# U96-SVM.net
KiCad netlist of a schematic drawn in EAGLE
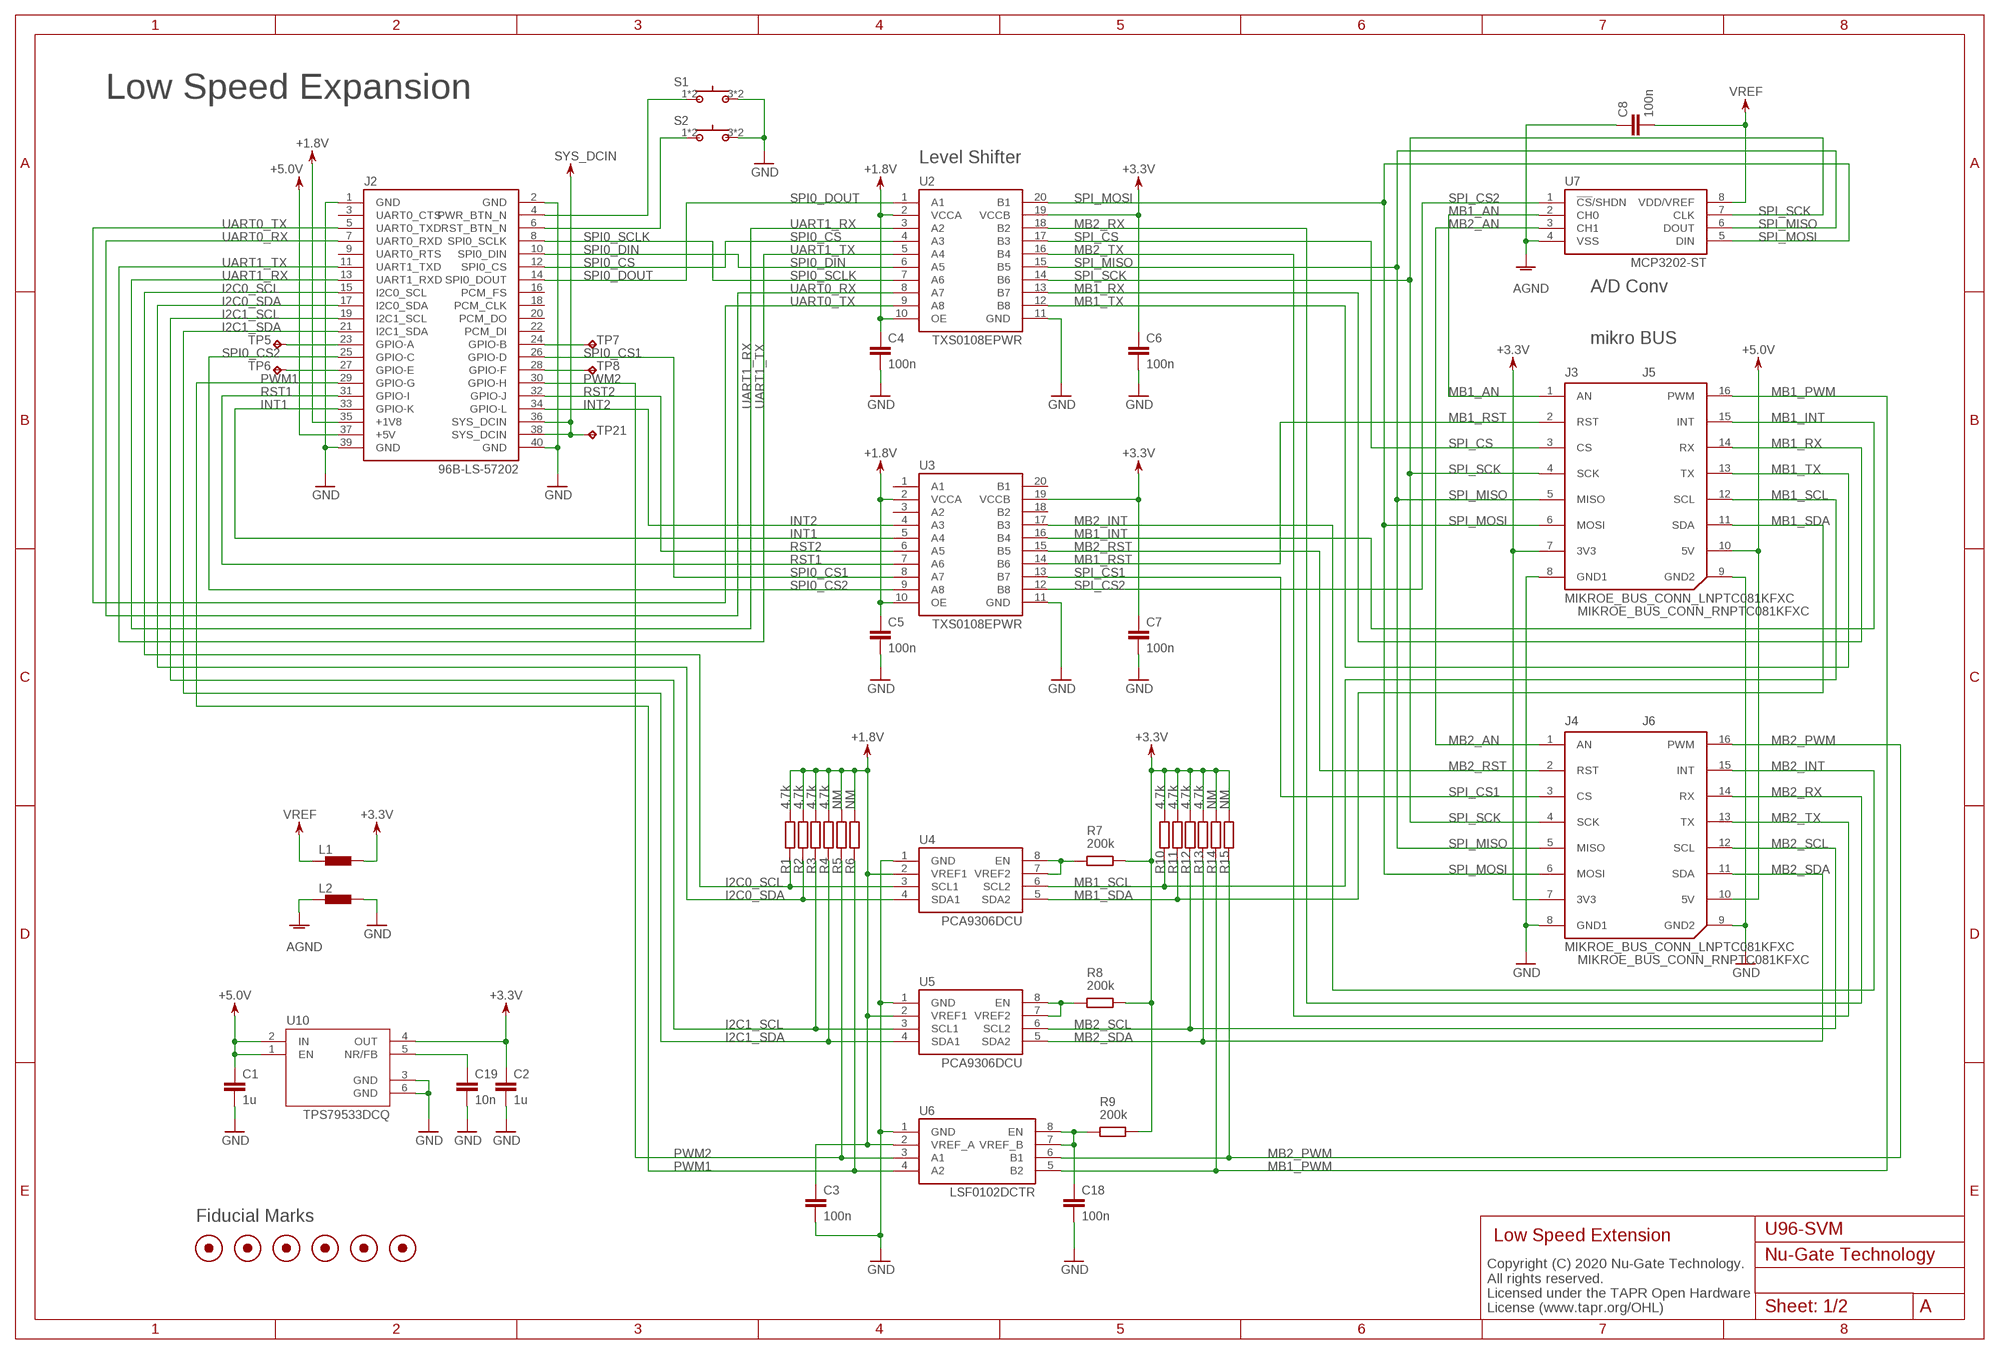
[diagram p0: schematic, sheet 1]
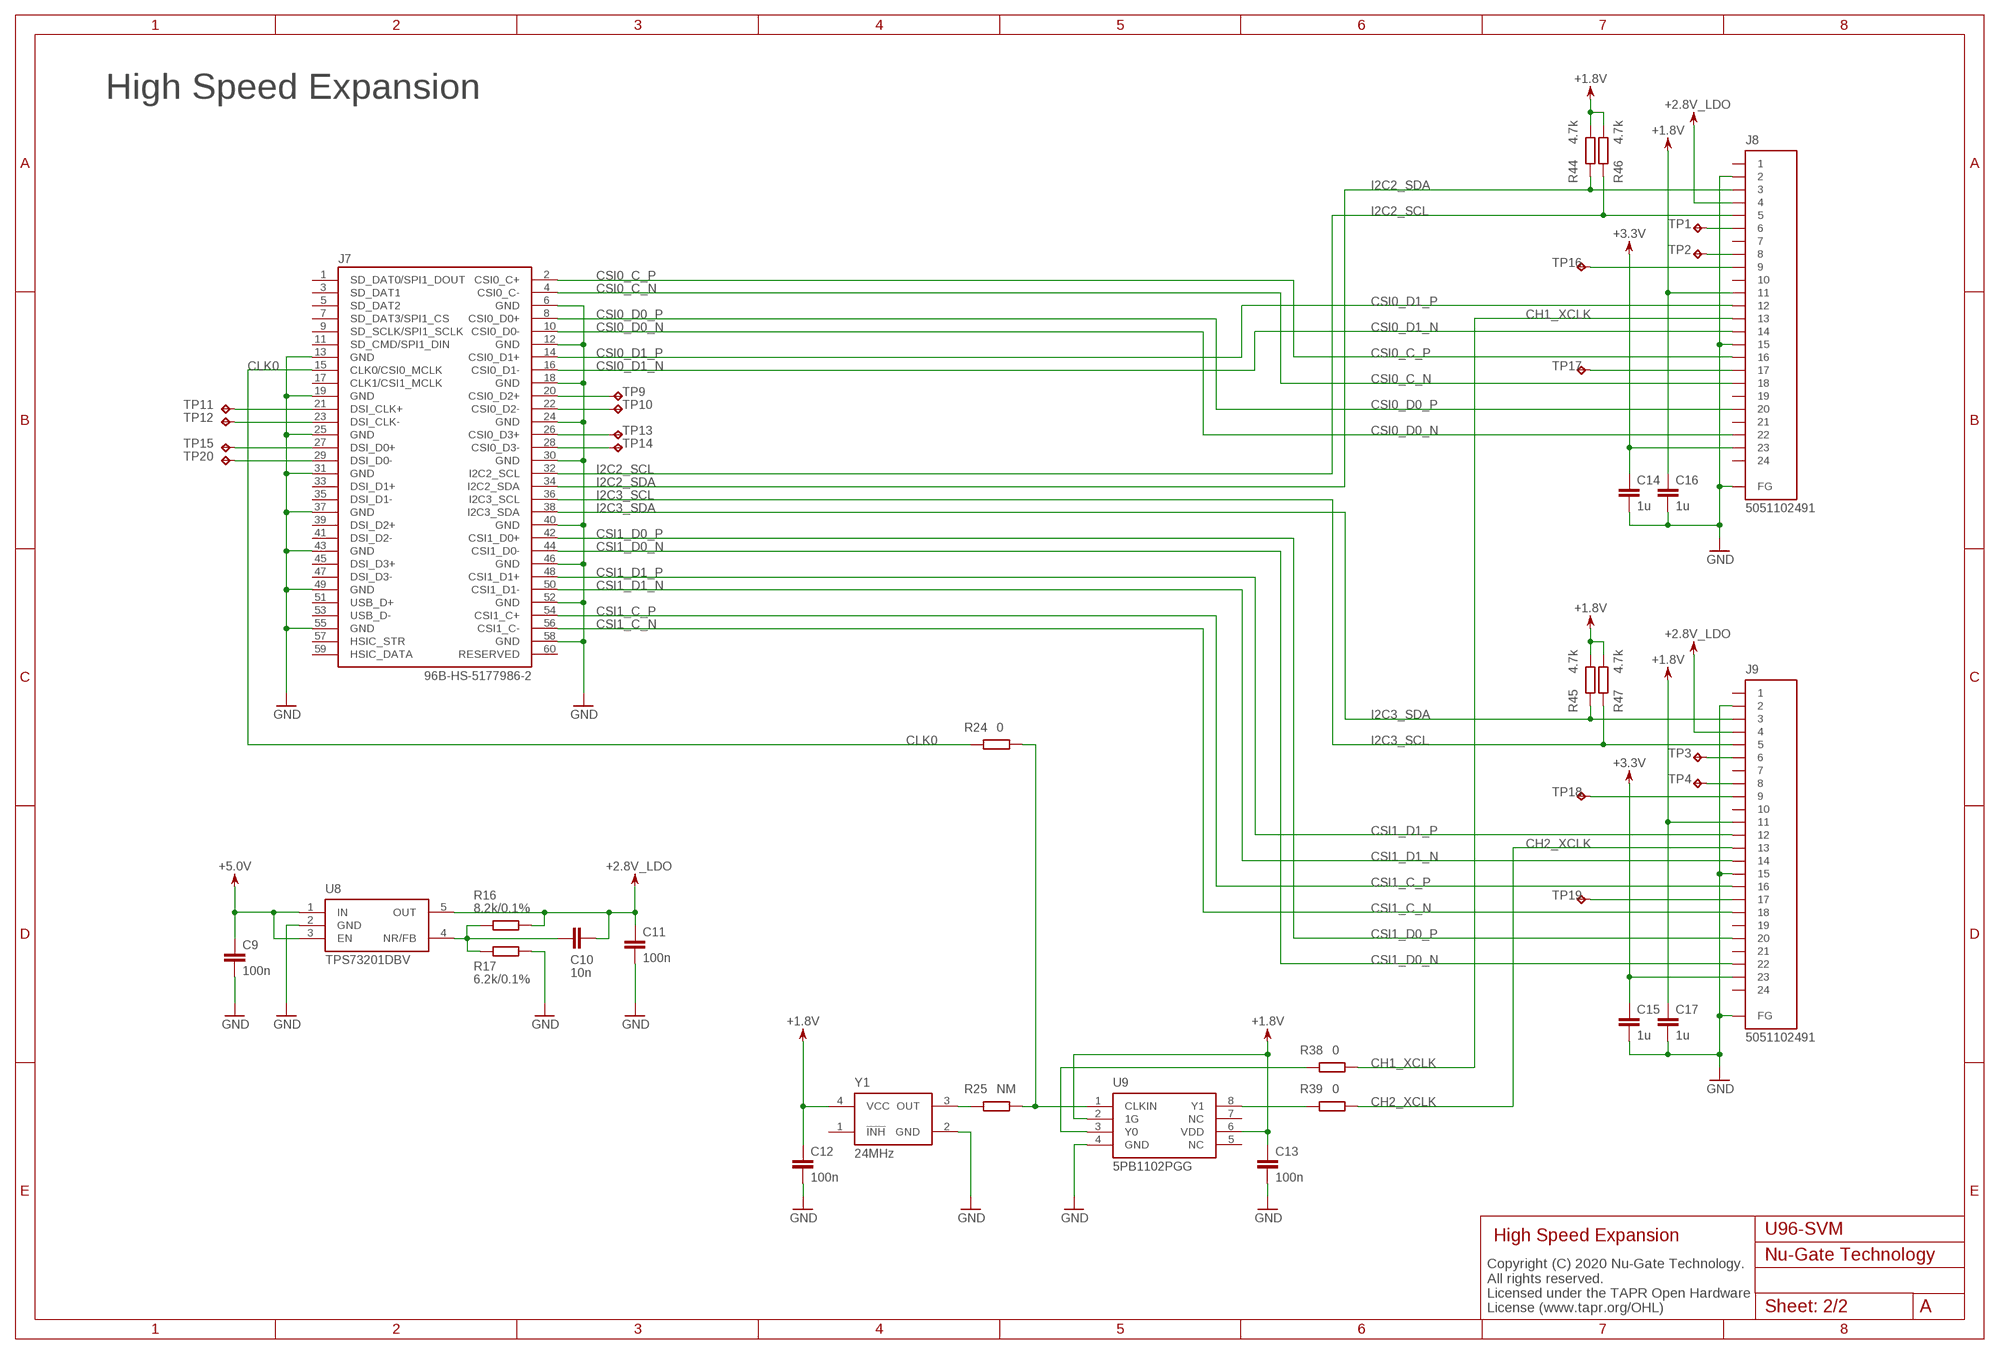
[diagram p1: schematic, sheet 2]

(export (version "E")
  (design (tool "Eeschema 10.0.6"))
  (components
    (comp (ref "C9")
      (value "100n")
      (footprint "eagle-import:C0402")
      (libsource (lib "eagle-import") (part "C-EUC0402"))
    )
    (comp (ref "C10")
      (value "10n")
      (footprint "eagle-import:C0402")
      (libsource (lib "eagle-import") (part "C-EUC0402"))
    )
    (comp (ref "C11")
      (value "100n")
      (footprint "eagle-import:C0402")
      (libsource (lib "eagle-import") (part "C-EUC0402"))
    )
    (comp (ref "C12")
      (value "100n")
      (footprint "eagle-import:C0402")
      (libsource (lib "eagle-import") (part "C-EUC0402"))
    )
    (comp (ref "C13")
      (value "100n")
      (footprint "eagle-import:C0402")
      (libsource (lib "eagle-import") (part "C-EUC0402"))
    )
    (comp (ref "C14")
      (value "1u")
      (footprint "eagle-import:C0402")
      (libsource (lib "eagle-import") (part "C-EUC0402"))
    )
    (comp (ref "C15")
      (value "1u")
      (footprint "eagle-import:C0402")
      (libsource (lib "eagle-import") (part "C-EUC0402"))
    )
    (comp (ref "C16")
      (value "1u")
      (footprint "eagle-import:C0402")
      (libsource (lib "eagle-import") (part "C-EUC0402"))
    )
    (comp (ref "C17")
      (value "1u")
      (footprint "eagle-import:C0402")
      (libsource (lib "eagle-import") (part "C-EUC0402"))
    )
    (comp (ref "J7")
      (value "96B-HS-5177986-2")
      (footprint "eagle-import:5177986-2")
      (libsource (lib "eagle-import") (part "96B-HS-5177986-2"))
    )
    (comp (ref "J8")
      (value "5051102491")
      (footprint "eagle-import:MO-5051102491")
      (libsource (lib "eagle-import") (part "5051102491"))
    )
    (comp (ref "J9")
      (value "5051102491")
      (footprint "eagle-import:MO-5051102491")
      (libsource (lib "eagle-import") (part "5051102491"))
    )
    (comp (ref "R16")
      (value "8.2k/0.1%")
      (footprint "eagle-import:R0402")
      (libsource (lib "eagle-import") (part "R-EU_R0402"))
    )
    (comp (ref "R17")
      (value "6.2k/0.1%")
      (footprint "eagle-import:R0402")
      (libsource (lib "eagle-import") (part "R-EU_R0402"))
    )
    (comp (ref "R24")
      (value "0")
      (footprint "eagle-import:R0402")
      (libsource (lib "eagle-import") (part "R-EU_R0402"))
    )
    (comp (ref "R25")
      (value "NM")
      (footprint "eagle-import:R0402")
      (libsource (lib "eagle-import") (part "R-EU_R0402"))
    )
    (comp (ref "R38")
      (value "0")
      (footprint "eagle-import:R0402")
      (libsource (lib "eagle-import") (part "R-EU_R0402"))
    )
    (comp (ref "R39")
      (value "0")
      (footprint "eagle-import:R0402")
      (libsource (lib "eagle-import") (part "R-EU_R0402"))
    )
    (comp (ref "R44")
      (value "4.7k")
      (footprint "eagle-import:R0402")
      (libsource (lib "eagle-import") (part "R-EU_R0402"))
    )
    (comp (ref "R45")
      (value "4.7k")
      (footprint "eagle-import:R0402")
      (libsource (lib "eagle-import") (part "R-EU_R0402"))
    )
    (comp (ref "R46")
      (value "4.7k")
      (footprint "eagle-import:R0402")
      (libsource (lib "eagle-import") (part "R-EU_R0402"))
    )
    (comp (ref "R47")
      (value "4.7k")
      (footprint "eagle-import:R0402")
      (libsource (lib "eagle-import") (part "R-EU_R0402"))
    )
    (comp (ref "TP1")
      (value "TPB1,27")
      (footprint "eagle-import:B1,27")
      (libsource (lib "eagle-import") (part "TPB1,27"))
    )
    (comp (ref "TP2")
      (value "TPB1,27")
      (footprint "eagle-import:B1,27")
      (libsource (lib "eagle-import") (part "TPB1,27"))
    )
    (comp (ref "TP3")
      (value "TPB1,27")
      (footprint "eagle-import:B1,27")
      (libsource (lib "eagle-import") (part "TPB1,27"))
    )
    (comp (ref "TP4")
      (value "TPB1,27")
      (footprint "eagle-import:B1,27")
      (libsource (lib "eagle-import") (part "TPB1,27"))
    )
    (comp (ref "TP9")
      (value "TPB1,27")
      (footprint "eagle-import:B1,27")
      (libsource (lib "eagle-import") (part "TPB1,27"))
    )
    (comp (ref "TP10")
      (value "TPB1,27")
      (footprint "eagle-import:B1,27")
      (libsource (lib "eagle-import") (part "TPB1,27"))
    )
    (comp (ref "TP11")
      (value "TPB1,27")
      (footprint "eagle-import:B1,27")
      (libsource (lib "eagle-import") (part "TPB1,27"))
    )
    (comp (ref "TP12")
      (value "TPB1,27")
      (footprint "eagle-import:B1,27")
      (libsource (lib "eagle-import") (part "TPB1,27"))
    )
    (comp (ref "TP13")
      (value "TPB1,27")
      (footprint "eagle-import:B1,27")
      (libsource (lib "eagle-import") (part "TPB1,27"))
    )
    (comp (ref "TP14")
      (value "TPB1,27")
      (footprint "eagle-import:B1,27")
      (libsource (lib "eagle-import") (part "TPB1,27"))
    )
    (comp (ref "TP15")
      (value "TPB1,27")
      (footprint "eagle-import:B1,27")
      (libsource (lib "eagle-import") (part "TPB1,27"))
    )
    (comp (ref "TP16")
      (value "TPB1,27")
      (footprint "eagle-import:B1,27")
      (libsource (lib "eagle-import") (part "TPB1,27"))
    )
    (comp (ref "TP17")
      (value "TPB1,27")
      (footprint "eagle-import:B1,27")
      (libsource (lib "eagle-import") (part "TPB1,27"))
    )
    (comp (ref "TP18")
      (value "TPB1,27")
      (footprint "eagle-import:B1,27")
      (libsource (lib "eagle-import") (part "TPB1,27"))
    )
    (comp (ref "TP19")
      (value "TPB1,27")
      (footprint "eagle-import:B1,27")
      (libsource (lib "eagle-import") (part "TPB1,27"))
    )
    (comp (ref "TP20")
      (value "TPB1,27")
      (footprint "eagle-import:B1,27")
      (libsource (lib "eagle-import") (part "TPB1,27"))
    )
    (comp (ref "U8")
      (value "TPS73201DBV")
      (footprint "eagle-import:TI-SOT23")
      (libsource (lib "eagle-import") (part "TPS732DBV01"))
    )
    (comp (ref "U9")
      (value "5PB1102PGG")
      (footprint "eagle-import:ID-TSSOP8")
      (libsource (lib "eagle-import") (part "5PB1102PGG"))
    )
    (comp (ref "Y1")
      (value "24MHz")
      (footprint "eagle-import:KC2520Z")
      (libsource (lib "eagle-import") (part "KC2520Z"))
    )
    (comp (ref "C1")
      (value "1u")
      (footprint "eagle-import:C0402")
      (libsource (lib "eagle-import") (part "C-EUC0402"))
    )
    (comp (ref "C2")
      (value "1u")
      (footprint "eagle-import:C0402")
      (libsource (lib "eagle-import") (part "C-EUC0402"))
    )
    (comp (ref "C3")
      (value "100n")
      (footprint "eagle-import:C0402")
      (libsource (lib "eagle-import") (part "C-EUC0402"))
    )
    (comp (ref "C4")
      (value "100n")
      (footprint "eagle-import:C0402")
      (libsource (lib "eagle-import") (part "C-EUC0402"))
    )
    (comp (ref "C5")
      (value "100n")
      (footprint "eagle-import:C0402")
      (libsource (lib "eagle-import") (part "C-EUC0402"))
    )
    (comp (ref "C6")
      (value "100n")
      (footprint "eagle-import:C0402")
      (libsource (lib "eagle-import") (part "C-EUC0402"))
    )
    (comp (ref "C7")
      (value "100n")
      (footprint "eagle-import:C0402")
      (libsource (lib "eagle-import") (part "C-EUC0402"))
    )
    (comp (ref "C8")
      (value "100n")
      (footprint "eagle-import:C0402")
      (libsource (lib "eagle-import") (part "C-EUC0402"))
    )
    (comp (ref "C18")
      (value "100n")
      (footprint "eagle-import:C0402")
      (libsource (lib "eagle-import") (part "C-EUC0402"))
    )
    (comp (ref "C19")
      (value "10n")
      (footprint "eagle-import:C0402")
      (libsource (lib "eagle-import") (part "C-EUC0402"))
    )
    (comp (ref "FID1")
      (value "FIDUCIAL")
      (footprint "eagle-import:FIDUCIAL_1MM")
      (libsource (lib "eagle-import") (part "FIDUCIAL"))
    )
    (comp (ref "FID2")
      (value "FIDUCIAL")
      (footprint "eagle-import:FIDUCIAL_1MM")
      (libsource (lib "eagle-import") (part "FIDUCIAL"))
    )
    (comp (ref "FID3")
      (value "FIDUCIAL")
      (footprint "eagle-import:FIDUCIAL_1MM")
      (libsource (lib "eagle-import") (part "FIDUCIAL"))
    )
    (comp (ref "FID4")
      (value "FIDUCIAL")
      (footprint "eagle-import:FIDUCIAL_1MM")
      (libsource (lib "eagle-import") (part "FIDUCIAL"))
    )
    (comp (ref "FID5")
      (value "FIDUCIAL")
      (footprint "eagle-import:FIDUCIAL_1MM")
      (libsource (lib "eagle-import") (part "FIDUCIAL"))
    )
    (comp (ref "FID6")
      (value "FIDUCIAL")
      (footprint "eagle-import:FIDUCIAL_1MM")
      (libsource (lib "eagle-import") (part "FIDUCIAL"))
    )
    (comp (ref "J2")
      (value "96B-LS-57202")
      (footprint "eagle-import:57202-G52-20LF")
      (libsource (lib "eagle-import") (part "96B-LS-57202"))
    )
    (comp (ref "J3")
      (value "MIKROE_BUS_CONN_LNPTC081KFXC")
      (footprint "eagle-import:MIKROBUS_HOST_CONN_L2")
      (libsource (lib "eagle-import") (part "MIKROE_BUS_CONN_LNPTC081KFXC"))
    )
    (comp (ref "J4")
      (value "MIKROE_BUS_CONN_LNPTC081KFXC")
      (footprint "eagle-import:MIKROBUS_HOST_CONN_L2")
      (libsource (lib "eagle-import") (part "MIKROE_BUS_CONN_LNPTC081KFXC"))
    )
    (comp (ref "J5")
      (value "MIKROE_BUS_CONN_RNPTC081KFXC")
      (footprint "eagle-import:MIKROBUS_HOST_CONN_R2")
      (libsource (lib "eagle-import") (part "MIKROE_BUS_CONN_RNPTC081KFXC"))
    )
    (comp (ref "J6")
      (value "MIKROE_BUS_CONN_RNPTC081KFXC")
      (footprint "eagle-import:MIKROBUS_HOST_CONN_R2")
      (libsource (lib "eagle-import") (part "MIKROE_BUS_CONN_RNPTC081KFXC"))
    )
    (comp (ref "L1")
      (value "BLM15AX")
      (footprint "eagle-import:0402")
      (libsource (lib "eagle-import") (part "BLM15AX"))
    )
    (comp (ref "L2")
      (value "BLM15AX")
      (footprint "eagle-import:0402")
      (libsource (lib "eagle-import") (part "BLM15AX"))
    )
    (comp (ref "R1")
      (value "4.7k")
      (footprint "eagle-import:R0402")
      (libsource (lib "eagle-import") (part "R-EU_R0402"))
    )
    (comp (ref "R2")
      (value "4.7k")
      (footprint "eagle-import:R0402")
      (libsource (lib "eagle-import") (part "R-EU_R0402"))
    )
    (comp (ref "R3")
      (value "4.7k")
      (footprint "eagle-import:R0402")
      (libsource (lib "eagle-import") (part "R-EU_R0402"))
    )
    (comp (ref "R4")
      (value "4.7k")
      (footprint "eagle-import:R0402")
      (libsource (lib "eagle-import") (part "R-EU_R0402"))
    )
    (comp (ref "R5")
      (value "NM")
      (footprint "eagle-import:R0402")
      (libsource (lib "eagle-import") (part "R-EU_R0402"))
    )
    (comp (ref "R6")
      (value "NM")
      (footprint "eagle-import:R0402")
      (libsource (lib "eagle-import") (part "R-EU_R0402"))
    )
    (comp (ref "R7")
      (value "200k")
      (footprint "eagle-import:R0402")
      (libsource (lib "eagle-import") (part "R-EU_R0402"))
    )
    (comp (ref "R8")
      (value "200k")
      (footprint "eagle-import:R0402")
      (libsource (lib "eagle-import") (part "R-EU_R0402"))
    )
    (comp (ref "R9")
      (value "200k")
      (footprint "eagle-import:R0402")
      (libsource (lib "eagle-import") (part "R-EU_R0402"))
    )
    (comp (ref "R10")
      (value "4.7k")
      (footprint "eagle-import:R0402")
      (libsource (lib "eagle-import") (part "R-EU_R0402"))
    )
    (comp (ref "R11")
      (value "4.7k")
      (footprint "eagle-import:R0402")
      (libsource (lib "eagle-import") (part "R-EU_R0402"))
    )
    (comp (ref "R12")
      (value "4.7k")
      (footprint "eagle-import:R0402")
      (libsource (lib "eagle-import") (part "R-EU_R0402"))
    )
    (comp (ref "R13")
      (value "4.7k")
      (footprint "eagle-import:R0402")
      (libsource (lib "eagle-import") (part "R-EU_R0402"))
    )
    (comp (ref "R14")
      (value "NM")
      (footprint "eagle-import:R0402")
      (libsource (lib "eagle-import") (part "R-EU_R0402"))
    )
    (comp (ref "R15")
      (value "NM")
      (footprint "eagle-import:R0402")
      (libsource (lib "eagle-import") (part "R-EU_R0402"))
    )
    (comp (ref "S1")
      (value "430181038816")
      (footprint "eagle-import:430181038816")
      (libsource (lib "eagle-import") (part "430181038816"))
    )
    (comp (ref "S2")
      (value "430181038816")
      (footprint "eagle-import:430181038816")
      (libsource (lib "eagle-import") (part "430181038816"))
    )
    (comp (ref "TP5")
      (value "TPB1,27")
      (footprint "eagle-import:B1,27")
      (libsource (lib "eagle-import") (part "TPB1,27"))
    )
    (comp (ref "TP6")
      (value "TPB1,27")
      (footprint "eagle-import:B1,27")
      (libsource (lib "eagle-import") (part "TPB1,27"))
    )
    (comp (ref "TP7")
      (value "TPB1,27")
      (footprint "eagle-import:B1,27")
      (libsource (lib "eagle-import") (part "TPB1,27"))
    )
    (comp (ref "TP8")
      (value "TPB1,27")
      (footprint "eagle-import:B1,27")
      (libsource (lib "eagle-import") (part "TPB1,27"))
    )
    (comp (ref "TP21")
      (value "TPB1,27")
      (footprint "eagle-import:B1,27")
      (libsource (lib "eagle-import") (part "TPB1,27"))
    )
    (comp (ref "U2")
      (value "TXS0108EPWR")
      (footprint "eagle-import:TI-PW20")
      (libsource (lib "eagle-import") (part "TXS0108EPWR"))
    )
    (comp (ref "U3")
      (value "TXS0108EPWR")
      (footprint "eagle-import:TI-PW20")
      (libsource (lib "eagle-import") (part "TXS0108EPWR"))
    )
    (comp (ref "U4")
      (value "PCA9306DCU")
      (footprint "eagle-import:TI-DCU8")
      (libsource (lib "eagle-import") (part "PCA9306DCU"))
    )
    (comp (ref "U5")
      (value "PCA9306DCU")
      (footprint "eagle-import:TI-DCU8")
      (libsource (lib "eagle-import") (part "PCA9306DCU"))
    )
    (comp (ref "U6")
      (value "LSF0102DCTR")
      (footprint "eagle-import:TI-DCT8")
      (libsource (lib "eagle-import") (part "LSF0102DCTR"))
    )
    (comp (ref "U7")
      (value "MCP3202-ST")
      (footprint "eagle-import:MC-ST8")
      (libsource (lib "eagle-import") (part "MCP3202-ST"))
    )
    (comp (ref "U10")
      (value "TPS79533DCQ")
      (footprint "eagle-import:TI-SOT223")
      (libsource (lib "eagle-import") (part "TPS79533DCQ"))
    )
  )
  (nets
    (net (code "1") (name "+1.8V") (class "Default")
      (node (ref "C12") (pin "1") (pinfunction "1_1") (pintype "passive"))
      (node (ref "C13") (pin "1") (pinfunction "1_1") (pintype "passive"))
      (node (ref "C16") (pin "1") (pinfunction "1_1") (pintype "passive"))
      (node (ref "C17") (pin "1") (pinfunction "1_1") (pintype "passive"))
      (node (ref "C3") (pin "1") (pinfunction "1_1") (pintype "passive"))
      (node (ref "C4") (pin "1") (pinfunction "1_1") (pintype "passive"))
      (node (ref "C5") (pin "1") (pinfunction "1_1") (pintype "passive"))
      (node (ref "J2") (pin "35") (pinfunction "+1V8_35") (pintype "bidirectional"))
      (node (ref "J8") (pin "11") (pinfunction "11_11") (pintype "bidirectional"))
      (node (ref "J9") (pin "11") (pinfunction "11_11") (pintype "bidirectional"))
      (node (ref "R1") (pin "2") (pinfunction "2_2") (pintype "passive"))
      (node (ref "R2") (pin "2") (pinfunction "2_2") (pintype "passive"))
      (node (ref "R3") (pin "2") (pinfunction "2_2") (pintype "passive"))
      (node (ref "R4") (pin "2") (pinfunction "2_2") (pintype "passive"))
      (node (ref "R44") (pin "2") (pinfunction "2_2") (pintype "passive"))
      (node (ref "R45") (pin "2") (pinfunction "2_2") (pintype "passive"))
      (node (ref "R46") (pin "2") (pinfunction "2_2") (pintype "passive"))
      (node (ref "R47") (pin "2") (pinfunction "2_2") (pintype "passive"))
      (node (ref "R5") (pin "2") (pinfunction "2_2") (pintype "passive"))
      (node (ref "R6") (pin "2") (pinfunction "2_2") (pintype "passive"))
      (node (ref "U2") (pin "10") (pinfunction "OE_10") (pintype "bidirectional"))
      (node (ref "U2") (pin "2") (pinfunction "VCCA_2") (pintype "bidirectional"))
      (node (ref "U3") (pin "10") (pinfunction "OE_10") (pintype "bidirectional"))
      (node (ref "U3") (pin "2") (pinfunction "VCCA_2") (pintype "bidirectional"))
      (node (ref "U4") (pin "2") (pinfunction "VREF1_2") (pintype "bidirectional"))
      (node (ref "U5") (pin "2") (pinfunction "VREF1_2") (pintype "bidirectional"))
      (node (ref "U6") (pin "2") (pinfunction "VREF_A_2") (pintype "bidirectional"))
      (node (ref "U9") (pin "2") (pinfunction "1G_2") (pintype "bidirectional"))
      (node (ref "U9") (pin "6") (pinfunction "VDD_6") (pintype "bidirectional"))
      (node (ref "Y1") (pin "4") (pinfunction "VCC_4") (pintype "power_in"))
    )
    (net (code "2") (name "+2.8V_LDO") (class "Default")
      (node (ref "C10") (pin "2") (pinfunction "2_2") (pintype "passive"))
      (node (ref "C11") (pin "1") (pinfunction "1_1") (pintype "passive"))
      (node (ref "J8") (pin "4") (pinfunction "4_4") (pintype "bidirectional"))
      (node (ref "J9") (pin "4") (pinfunction "4_4") (pintype "bidirectional"))
      (node (ref "R16") (pin "2") (pinfunction "2_2") (pintype "passive"))
      (node (ref "U8") (pin "5") (pinfunction "OUT_5") (pintype "power_in"))
    )
    (net (code "3") (name "+3.3V") (class "Default")
      (node (ref "C14") (pin "1") (pinfunction "1_1") (pintype "passive"))
      (node (ref "C15") (pin "1") (pinfunction "1_1") (pintype "passive"))
      (node (ref "C2") (pin "1") (pinfunction "1_1") (pintype "passive"))
      (node (ref "C6") (pin "1") (pinfunction "1_1") (pintype "passive"))
      (node (ref "C7") (pin "1") (pinfunction "1_1") (pintype "passive"))
      (node (ref "J3") (pin "7") (pinfunction "3V3_7") (pintype "bidirectional"))
      (node (ref "J4") (pin "7") (pinfunction "3V3_7") (pintype "bidirectional"))
      (node (ref "J8") (pin "23") (pinfunction "23_23") (pintype "bidirectional"))
      (node (ref "J9") (pin "23") (pinfunction "23_23") (pintype "bidirectional"))
      (node (ref "L1") (pin "2") (pinfunction "2_2") (pintype "passive"))
      (node (ref "R10") (pin "2") (pinfunction "2_2") (pintype "passive"))
      (node (ref "R11") (pin "2") (pinfunction "2_2") (pintype "passive"))
      (node (ref "R12") (pin "2") (pinfunction "2_2") (pintype "passive"))
      (node (ref "R13") (pin "2") (pinfunction "2_2") (pintype "passive"))
      (node (ref "R14") (pin "2") (pinfunction "2_2") (pintype "passive"))
      (node (ref "R15") (pin "2") (pinfunction "2_2") (pintype "passive"))
      (node (ref "R7") (pin "2") (pinfunction "2_2") (pintype "passive"))
      (node (ref "R8") (pin "2") (pinfunction "2_2") (pintype "passive"))
      (node (ref "R9") (pin "2") (pinfunction "2_2") (pintype "passive"))
      (node (ref "U10") (pin "4") (pinfunction "OUT_4") (pintype "bidirectional"))
      (node (ref "U2") (pin "19") (pinfunction "VCCB_19") (pintype "bidirectional"))
      (node (ref "U3") (pin "19") (pinfunction "VCCB_19") (pintype "bidirectional"))
    )
    (net (code "4") (name "+5.0V") (class "Default")
      (node (ref "C1") (pin "1") (pinfunction "1_1") (pintype "passive"))
      (node (ref "C9") (pin "1") (pinfunction "1_1") (pintype "passive"))
      (node (ref "J2") (pin "37") (pinfunction "+5V_37") (pintype "bidirectional"))
      (node (ref "J5") (pin "10") (pinfunction "5V_10") (pintype "bidirectional"))
      (node (ref "J6") (pin "10") (pinfunction "5V_10") (pintype "bidirectional"))
      (node (ref "U10") (pin "1") (pinfunction "EN_1") (pintype "bidirectional"))
      (node (ref "U10") (pin "2") (pinfunction "IN_2") (pintype "bidirectional"))
      (node (ref "U8") (pin "1") (pinfunction "IN_1") (pintype "power_in"))
      (node (ref "U8") (pin "3") (pinfunction "EN_3") (pintype "input"))
    )
    (net (code "5") (name "AGND") (class "Default")
      (node (ref "C8") (pin "1") (pinfunction "1_1") (pintype "passive"))
      (node (ref "L2") (pin "1") (pinfunction "1_1") (pintype "passive"))
      (node (ref "U7") (pin "4") (pinfunction "VSS_4") (pintype "bidirectional"))
    )
    (net (code "6") (name "CH1_XCLK") (class "Default")
      (node (ref "J8") (pin "13") (pinfunction "13_13") (pintype "bidirectional"))
      (node (ref "R38") (pin "2") (pinfunction "2_2") (pintype "passive"))
    )
    (net (code "7") (name "CH2_XCLK") (class "Default")
      (node (ref "J9") (pin "13") (pinfunction "13_13") (pintype "bidirectional"))
      (node (ref "R39") (pin "2") (pinfunction "2_2") (pintype "passive"))
    )
    (net (code "8") (name "CLK0") (class "Default")
      (node (ref "J7") (pin "15") (pinfunction "CLK0/CSI0_MCLK_15") (pintype "bidirectional"))
      (node (ref "R24") (pin "1") (pinfunction "1_1") (pintype "passive"))
    )
    (net (code "9") (name "CSI0_C_N") (class "Default")
      (node (ref "J7") (pin "4") (pinfunction "CSI0_C-_4") (pintype "bidirectional"))
      (node (ref "J8") (pin "18") (pinfunction "18_18") (pintype "bidirectional"))
    )
    (net (code "10") (name "CSI0_C_P") (class "Default")
      (node (ref "J7") (pin "2") (pinfunction "CSI0_C+_2") (pintype "bidirectional"))
      (node (ref "J8") (pin "16") (pinfunction "16_16") (pintype "bidirectional"))
    )
    (net (code "11") (name "CSI0_D0_N") (class "Default")
      (node (ref "J7") (pin "10") (pinfunction "CSI0_D0-_10") (pintype "bidirectional"))
      (node (ref "J8") (pin "22") (pinfunction "22_22") (pintype "bidirectional"))
    )
    (net (code "12") (name "CSI0_D0_P") (class "Default")
      (node (ref "J7") (pin "8") (pinfunction "CSI0_D0+_8") (pintype "bidirectional"))
      (node (ref "J8") (pin "20") (pinfunction "20_20") (pintype "bidirectional"))
    )
    (net (code "13") (name "CSI0_D1_N") (class "Default")
      (node (ref "J7") (pin "16") (pinfunction "CSI0_D1-_16") (pintype "bidirectional"))
      (node (ref "J8") (pin "14") (pinfunction "14_14") (pintype "bidirectional"))
    )
    (net (code "14") (name "CSI0_D1_P") (class "Default")
      (node (ref "J7") (pin "14") (pinfunction "CSI0_D1+_14") (pintype "bidirectional"))
      (node (ref "J8") (pin "12") (pinfunction "12_12") (pintype "bidirectional"))
    )
    (net (code "15") (name "CSI1_C_N") (class "Default")
      (node (ref "J7") (pin "56") (pinfunction "CSI1_C-_56") (pintype "bidirectional"))
      (node (ref "J9") (pin "18") (pinfunction "18_18") (pintype "bidirectional"))
    )
    (net (code "16") (name "CSI1_C_P") (class "Default")
      (node (ref "J7") (pin "54") (pinfunction "CSI1_C+_54") (pintype "bidirectional"))
      (node (ref "J9") (pin "16") (pinfunction "16_16") (pintype "bidirectional"))
    )
    (net (code "17") (name "CSI1_D0_N") (class "Default")
      (node (ref "J7") (pin "44") (pinfunction "CSI1_D0-_44") (pintype "bidirectional"))
      (node (ref "J9") (pin "22") (pinfunction "22_22") (pintype "bidirectional"))
    )
    (net (code "18") (name "CSI1_D0_P") (class "Default")
      (node (ref "J7") (pin "42") (pinfunction "CSI1_D0+_42") (pintype "bidirectional"))
      (node (ref "J9") (pin "20") (pinfunction "20_20") (pintype "bidirectional"))
    )
    (net (code "19") (name "CSI1_D1_N") (class "Default")
      (node (ref "J7") (pin "50") (pinfunction "CSI1_D1-_50") (pintype "bidirectional"))
      (node (ref "J9") (pin "14") (pinfunction "14_14") (pintype "bidirectional"))
    )
    (net (code "20") (name "CSI1_D1_P") (class "Default")
      (node (ref "J7") (pin "48") (pinfunction "CSI1_D1+_48") (pintype "bidirectional"))
      (node (ref "J9") (pin "12") (pinfunction "12_12") (pintype "bidirectional"))
    )
    (net (code "21") (name "GND") (class "Default")
      (node (ref "C1") (pin "2") (pinfunction "2_2") (pintype "passive"))
      (node (ref "C11") (pin "2") (pinfunction "2_2") (pintype "passive"))
      (node (ref "C12") (pin "2") (pinfunction "2_2") (pintype "passive"))
      (node (ref "C13") (pin "2") (pinfunction "2_2") (pintype "passive"))
      (node (ref "C14") (pin "2") (pinfunction "2_2") (pintype "passive"))
      (node (ref "C15") (pin "2") (pinfunction "2_2") (pintype "passive"))
      (node (ref "C16") (pin "2") (pinfunction "2_2") (pintype "passive"))
      (node (ref "C17") (pin "2") (pinfunction "2_2") (pintype "passive"))
      (node (ref "C18") (pin "2") (pinfunction "2_2") (pintype "passive"))
      (node (ref "C19") (pin "2") (pinfunction "2_2") (pintype "passive"))
      (node (ref "C2") (pin "2") (pinfunction "2_2") (pintype "passive"))
      (node (ref "C3") (pin "2") (pinfunction "2_2") (pintype "passive"))
      (node (ref "C4") (pin "2") (pinfunction "2_2") (pintype "passive"))
      (node (ref "C5") (pin "2") (pinfunction "2_2") (pintype "passive"))
      (node (ref "C6") (pin "2") (pinfunction "2_2") (pintype "passive"))
      (node (ref "C7") (pin "2") (pinfunction "2_2") (pintype "passive"))
      (node (ref "C9") (pin "2") (pinfunction "2_2") (pintype "passive"))
      (node (ref "J2") (pin "1") (pinfunction "GND_1") (pintype "bidirectional"))
      (node (ref "J2") (pin "2") (pinfunction "GND_2") (pintype "bidirectional"))
      (node (ref "J2") (pin "39") (pinfunction "GND_39") (pintype "bidirectional"))
      (node (ref "J2") (pin "40") (pinfunction "GND_40") (pintype "bidirectional"))
      (node (ref "J3") (pin "8") (pinfunction "GND1_8") (pintype "bidirectional"))
      (node (ref "J4") (pin "8") (pinfunction "GND1_8") (pintype "bidirectional"))
      (node (ref "J5") (pin "9") (pinfunction "GND2_9") (pintype "bidirectional"))
      (node (ref "J6") (pin "9") (pinfunction "GND2_9") (pintype "bidirectional"))
      (node (ref "J7") (pin "12") (pinfunction "GND_12") (pintype "bidirectional"))
      (node (ref "J7") (pin "13") (pinfunction "GND_13") (pintype "bidirectional"))
      (node (ref "J7") (pin "18") (pinfunction "GND_18") (pintype "bidirectional"))
      (node (ref "J7") (pin "19") (pinfunction "GND_19") (pintype "bidirectional"))
      (node (ref "J7") (pin "24") (pinfunction "GND_24") (pintype "bidirectional"))
      (node (ref "J7") (pin "25") (pinfunction "GND_25") (pintype "bidirectional"))
      (node (ref "J7") (pin "30") (pinfunction "GND_30") (pintype "bidirectional"))
      (node (ref "J7") (pin "31") (pinfunction "GND_31") (pintype "bidirectional"))
      (node (ref "J7") (pin "37") (pinfunction "GND_37") (pintype "bidirectional"))
      (node (ref "J7") (pin "40") (pinfunction "GND_40") (pintype "bidirectional"))
      (node (ref "J7") (pin "43") (pinfunction "GND_43") (pintype "bidirectional"))
      (node (ref "J7") (pin "46") (pinfunction "GND_46") (pintype "bidirectional"))
      (node (ref "J7") (pin "49") (pinfunction "GND_49") (pintype "bidirectional"))
      (node (ref "J7") (pin "52") (pinfunction "GND_52") (pintype "bidirectional"))
      (node (ref "J7") (pin "55") (pinfunction "GND_55") (pintype "bidirectional"))
      (node (ref "J7") (pin "58") (pinfunction "GND_58") (pintype "bidirectional"))
      (node (ref "J7") (pin "6") (pinfunction "GND_6") (pintype "bidirectional"))
      (node (ref "J8") (pin "15") (pinfunction "15_15") (pintype "bidirectional"))
      (node (ref "J8") (pin "2") (pinfunction "2_2") (pintype "bidirectional"))
      (node (ref "J8") (pin "FG@1") (pinfunction "FG_FG@1") (pintype "bidirectional"))
      (node (ref "J8") (pin "FG@2") (pinfunction "FG_FG@2") (pintype "bidirectional"))
      (node (ref "J9") (pin "15") (pinfunction "15_15") (pintype "bidirectional"))
      (node (ref "J9") (pin "2") (pinfunction "2_2") (pintype "bidirectional"))
      (node (ref "J9") (pin "FG@1") (pinfunction "FG_FG@1") (pintype "bidirectional"))
      (node (ref "J9") (pin "FG@2") (pinfunction "FG_FG@2") (pintype "bidirectional"))
      (node (ref "L2") (pin "2") (pinfunction "2_2") (pintype "passive"))
      (node (ref "R17") (pin "2") (pinfunction "2_2") (pintype "passive"))
      (node (ref "S1") (pin "3") (pinfunction "P$2_3") (pintype "bidirectional"))
      (node (ref "S1") (pin "4") (pinfunction "P$2_4") (pintype "bidirectional"))
      (node (ref "S2") (pin "3") (pinfunction "P$2_3") (pintype "bidirectional"))
      (node (ref "S2") (pin "4") (pinfunction "P$2_4") (pintype "bidirectional"))
      (node (ref "U10") (pin "3") (pinfunction "GND_3") (pintype "bidirectional"))
      (node (ref "U10") (pin "6") (pinfunction "GND_6") (pintype "bidirectional"))
      (node (ref "U2") (pin "11") (pinfunction "GND_11") (pintype "bidirectional"))
      (node (ref "U3") (pin "11") (pinfunction "GND_11") (pintype "bidirectional"))
      (node (ref "U4") (pin "1") (pinfunction "GND_1") (pintype "bidirectional"))
      (node (ref "U5") (pin "1") (pinfunction "GND_1") (pintype "bidirectional"))
      (node (ref "U6") (pin "1") (pinfunction "GND_1") (pintype "bidirectional"))
      (node (ref "U8") (pin "2") (pinfunction "GND_2") (pintype "power_in"))
      (node (ref "U9") (pin "4") (pinfunction "GND_4") (pintype "bidirectional"))
      (node (ref "Y1") (pin "2") (pinfunction "GND_2") (pintype "power_in"))
    )
    (net (code "22") (name "I2C0_SCL") (class "Default")
      (node (ref "J2") (pin "15") (pinfunction "I2C0_SCL_15") (pintype "bidirectional"))
      (node (ref "R1") (pin "1") (pinfunction "1_1") (pintype "passive"))
      (node (ref "U4") (pin "3") (pinfunction "SCL1_3") (pintype "bidirectional"))
    )
    (net (code "23") (name "I2C0_SDA") (class "Default")
      (node (ref "J2") (pin "17") (pinfunction "I2C0_SDA_17") (pintype "bidirectional"))
      (node (ref "R2") (pin "1") (pinfunction "1_1") (pintype "passive"))
      (node (ref "U4") (pin "4") (pinfunction "SDA1_4") (pintype "bidirectional"))
    )
    (net (code "24") (name "I2C1_SCL") (class "Default")
      (node (ref "J2") (pin "19") (pinfunction "I2C1_SCL_19") (pintype "bidirectional"))
      (node (ref "R3") (pin "1") (pinfunction "1_1") (pintype "passive"))
      (node (ref "U5") (pin "3") (pinfunction "SCL1_3") (pintype "bidirectional"))
    )
    (net (code "25") (name "I2C1_SDA") (class "Default")
      (node (ref "J2") (pin "21") (pinfunction "I2C1_SDA_21") (pintype "bidirectional"))
      (node (ref "R4") (pin "1") (pinfunction "1_1") (pintype "passive"))
      (node (ref "U5") (pin "4") (pinfunction "SDA1_4") (pintype "bidirectional"))
    )
    (net (code "26") (name "I2C2_SCL") (class "Default")
      (node (ref "J7") (pin "32") (pinfunction "I2C2_SCL_32") (pintype "bidirectional"))
      (node (ref "J8") (pin "5") (pinfunction "5_5") (pintype "bidirectional"))
      (node (ref "R46") (pin "1") (pinfunction "1_1") (pintype "passive"))
    )
    (net (code "27") (name "I2C2_SDA") (class "Default")
      (node (ref "J7") (pin "34") (pinfunction "I2C2_SDA_34") (pintype "bidirectional"))
      (node (ref "J8") (pin "3") (pinfunction "3_3") (pintype "bidirectional"))
      (node (ref "R44") (pin "1") (pinfunction "1_1") (pintype "passive"))
    )
    (net (code "28") (name "I2C3_SCL") (class "Default")
      (node (ref "J7") (pin "36") (pinfunction "I2C3_SCL_36") (pintype "bidirectional"))
      (node (ref "J9") (pin "5") (pinfunction "5_5") (pintype "bidirectional"))
      (node (ref "R47") (pin "1") (pinfunction "1_1") (pintype "passive"))
    )
    (net (code "29") (name "I2C3_SDA") (class "Default")
      (node (ref "J7") (pin "38") (pinfunction "I2C3_SDA_38") (pintype "bidirectional"))
      (node (ref "J9") (pin "3") (pinfunction "3_3") (pintype "bidirectional"))
      (node (ref "R45") (pin "1") (pinfunction "1_1") (pintype "passive"))
    )
    (net (code "30") (name "INT1") (class "Default")
      (node (ref "J2") (pin "33") (pinfunction "GPIO-K_33") (pintype "bidirectional"))
      (node (ref "U3") (pin "5") (pinfunction "A4_5") (pintype "bidirectional"))
    )
    (net (code "31") (name "INT2") (class "Default")
      (node (ref "J2") (pin "34") (pinfunction "GPIO-L_34") (pintype "bidirectional"))
      (node (ref "U3") (pin "4") (pinfunction "A3_4") (pintype "bidirectional"))
    )
    (net (code "32") (name "MB1_AN") (class "Default")
      (node (ref "J3") (pin "1") (pinfunction "AN_1") (pintype "bidirectional"))
      (node (ref "U7") (pin "2") (pinfunction "CH0_2") (pintype "bidirectional"))
    )
    (net (code "33") (name "MB1_INT") (class "Default")
      (node (ref "J5") (pin "15") (pinfunction "INT_15") (pintype "bidirectional"))
      (node (ref "U3") (pin "16") (pinfunction "B4_16") (pintype "bidirectional"))
    )
    (net (code "34") (name "MB1_PWM") (class "Default")
      (node (ref "J5") (pin "16") (pinfunction "PWM_16") (pintype "bidirectional"))
      (node (ref "R14") (pin "1") (pinfunction "1_1") (pintype "passive"))
      (node (ref "U6") (pin "5") (pinfunction "B2_5") (pintype "bidirectional"))
    )
    (net (code "35") (name "MB1_RST") (class "Default")
      (node (ref "J3") (pin "2") (pinfunction "RST_2") (pintype "bidirectional"))
      (node (ref "U3") (pin "14") (pinfunction "B6_14") (pintype "bidirectional"))
    )
    (net (code "36") (name "MB1_RX") (class "Default")
      (node (ref "J5") (pin "14") (pinfunction "RX_14") (pintype "bidirectional"))
      (node (ref "U2") (pin "13") (pinfunction "B7_13") (pintype "bidirectional"))
    )
    (net (code "37") (name "MB1_SCL") (class "Default")
      (node (ref "J5") (pin "12") (pinfunction "SCL_12") (pintype "bidirectional"))
      (node (ref "R10") (pin "1") (pinfunction "1_1") (pintype "passive"))
      (node (ref "U4") (pin "6") (pinfunction "SCL2_6") (pintype "bidirectional"))
    )
    (net (code "38") (name "MB1_SDA") (class "Default")
      (node (ref "J5") (pin "11") (pinfunction "SDA_11") (pintype "bidirectional"))
      (node (ref "R11") (pin "1") (pinfunction "1_1") (pintype "passive"))
      (node (ref "U4") (pin "5") (pinfunction "SDA2_5") (pintype "bidirectional"))
    )
    (net (code "39") (name "MB1_TX") (class "Default")
      (node (ref "J5") (pin "13") (pinfunction "TX_13") (pintype "bidirectional"))
      (node (ref "U2") (pin "12") (pinfunction "B8_12") (pintype "bidirectional"))
    )
    (net (code "40") (name "MB2_AN") (class "Default")
      (node (ref "J4") (pin "1") (pinfunction "AN_1") (pintype "bidirectional"))
      (node (ref "U7") (pin "3") (pinfunction "CH1_3") (pintype "bidirectional"))
    )
    (net (code "41") (name "MB2_INT") (class "Default")
      (node (ref "J6") (pin "15") (pinfunction "INT_15") (pintype "bidirectional"))
      (node (ref "U3") (pin "17") (pinfunction "B3_17") (pintype "bidirectional"))
    )
    (net (code "42") (name "MB2_PWM") (class "Default")
      (node (ref "J6") (pin "16") (pinfunction "PWM_16") (pintype "bidirectional"))
      (node (ref "R15") (pin "1") (pinfunction "1_1") (pintype "passive"))
      (node (ref "U6") (pin "6") (pinfunction "B1_6") (pintype "bidirectional"))
    )
    (net (code "43") (name "MB2_RST") (class "Default")
      (node (ref "J4") (pin "2") (pinfunction "RST_2") (pintype "bidirectional"))
      (node (ref "U3") (pin "15") (pinfunction "B5_15") (pintype "bidirectional"))
    )
    (net (code "44") (name "MB2_RX") (class "Default")
      (node (ref "J6") (pin "14") (pinfunction "RX_14") (pintype "bidirectional"))
      (node (ref "U2") (pin "18") (pinfunction "B2_18") (pintype "bidirectional"))
    )
    (net (code "45") (name "MB2_SCL") (class "Default")
      (node (ref "J6") (pin "12") (pinfunction "SCL_12") (pintype "bidirectional"))
      (node (ref "R12") (pin "1") (pinfunction "1_1") (pintype "passive"))
      (node (ref "U5") (pin "6") (pinfunction "SCL2_6") (pintype "bidirectional"))
    )
    (net (code "46") (name "MB2_SDA") (class "Default")
      (node (ref "J6") (pin "11") (pinfunction "SDA_11") (pintype "bidirectional"))
      (node (ref "R13") (pin "1") (pinfunction "1_1") (pintype "passive"))
      (node (ref "U5") (pin "5") (pinfunction "SDA2_5") (pintype "bidirectional"))
    )
    (net (code "47") (name "MB2_TX") (class "Default")
      (node (ref "J6") (pin "13") (pinfunction "TX_13") (pintype "bidirectional"))
      (node (ref "U2") (pin "16") (pinfunction "B4_16") (pintype "bidirectional"))
    )
    (net (code "48") (name "Net-(J2-GPIO-A)") (class "Default")
      (node (ref "J2") (pin "23") (pinfunction "GPIO-A_23") (pintype "bidirectional"))
      (node (ref "TP5") (pin "TP") (pinfunction "TP_TP") (pintype "input"))
    )
    (net (code "49") (name "Net-(J2-GPIO-B)") (class "Default")
      (node (ref "J2") (pin "24") (pinfunction "GPIO-B_24") (pintype "bidirectional"))
      (node (ref "TP7") (pin "TP") (pinfunction "TP_TP") (pintype "input"))
    )
    (net (code "50") (name "Net-(J2-GPIO-E)") (class "Default")
      (node (ref "J2") (pin "27") (pinfunction "GPIO-E_27") (pintype "bidirectional"))
      (node (ref "TP6") (pin "TP") (pinfunction "TP_TP") (pintype "input"))
    )
    (net (code "51") (name "Net-(J2-GPIO-F)") (class "Default")
      (node (ref "J2") (pin "28") (pinfunction "GPIO-F_28") (pintype "bidirectional"))
      (node (ref "TP8") (pin "TP") (pinfunction "TP_TP") (pintype "input"))
    )
    (net (code "52") (name "Net-(J2-PWR_BTN_N)") (class "Default")
      (node (ref "J2") (pin "4") (pinfunction "PWR_BTN_N_4") (pintype "bidirectional"))
      (node (ref "S1") (pin "1") (pinfunction "P$1_1") (pintype "bidirectional"))
      (node (ref "S1") (pin "2") (pinfunction "P$1_2") (pintype "bidirectional"))
    )
    (net (code "53") (name "Net-(J2-RST_BTN_N)") (class "Default")
      (node (ref "J2") (pin "6") (pinfunction "RST_BTN_N_6") (pintype "bidirectional"))
      (node (ref "S2") (pin "1") (pinfunction "P$1_1") (pintype "bidirectional"))
      (node (ref "S2") (pin "2") (pinfunction "P$1_2") (pintype "bidirectional"))
    )
    (net (code "54") (name "Net-(J7-CSI0_D2+)") (class "Default")
      (node (ref "J7") (pin "20") (pinfunction "CSI0_D2+_20") (pintype "bidirectional"))
      (node (ref "TP9") (pin "TP") (pinfunction "TP_TP") (pintype "input"))
    )
    (net (code "55") (name "Net-(J7-CSI0_D2-)") (class "Default")
      (node (ref "J7") (pin "22") (pinfunction "CSI0_D2-_22") (pintype "bidirectional"))
      (node (ref "TP10") (pin "TP") (pinfunction "TP_TP") (pintype "input"))
    )
    (net (code "56") (name "Net-(J7-CSI0_D3+)") (class "Default")
      (node (ref "J7") (pin "26") (pinfunction "CSI0_D3+_26") (pintype "bidirectional"))
      (node (ref "TP13") (pin "TP") (pinfunction "TP_TP") (pintype "input"))
    )
    (net (code "57") (name "Net-(J7-CSI0_D3-)") (class "Default")
      (node (ref "J7") (pin "28") (pinfunction "CSI0_D3-_28") (pintype "bidirectional"))
      (node (ref "TP14") (pin "TP") (pinfunction "TP_TP") (pintype "input"))
    )
    (net (code "58") (name "Net-(J7-DSI_CLK+)") (class "Default")
      (node (ref "J7") (pin "21") (pinfunction "DSI_CLK+_21") (pintype "bidirectional"))
      (node (ref "TP11") (pin "TP") (pinfunction "TP_TP") (pintype "input"))
    )
    (net (code "59") (name "Net-(J7-DSI_CLK-)") (class "Default")
      (node (ref "J7") (pin "23") (pinfunction "DSI_CLK-_23") (pintype "bidirectional"))
      (node (ref "TP12") (pin "TP") (pinfunction "TP_TP") (pintype "input"))
    )
    (net (code "60") (name "Net-(J7-DSI_D0+)") (class "Default")
      (node (ref "J7") (pin "27") (pinfunction "DSI_D0+_27") (pintype "bidirectional"))
      (node (ref "TP15") (pin "TP") (pinfunction "TP_TP") (pintype "input"))
    )
    (net (code "61") (name "Net-(J7-DSI_D0-)") (class "Default")
      (node (ref "J7") (pin "29") (pinfunction "DSI_D0-_29") (pintype "bidirectional"))
      (node (ref "TP20") (pin "TP") (pinfunction "TP_TP") (pintype "input"))
    )
    (net (code "62") (name "Net-(J8-Pad6)") (class "Default")
      (node (ref "J8") (pin "6") (pinfunction "6_6") (pintype "bidirectional"))
      (node (ref "TP1") (pin "TP") (pinfunction "TP_TP") (pintype "input"))
    )
    (net (code "63") (name "Net-(J8-Pad8)") (class "Default")
      (node (ref "J8") (pin "8") (pinfunction "8_8") (pintype "bidirectional"))
      (node (ref "TP2") (pin "TP") (pinfunction "TP_TP") (pintype "input"))
    )
    (net (code "64") (name "Net-(J8-Pad9)") (class "Default")
      (node (ref "J8") (pin "9") (pinfunction "9_9") (pintype "bidirectional"))
      (node (ref "TP16") (pin "TP") (pinfunction "TP_TP") (pintype "input"))
    )
    (net (code "65") (name "Net-(J8-Pad17)") (class "Default")
      (node (ref "J8") (pin "17") (pinfunction "17_17") (pintype "bidirectional"))
      (node (ref "TP17") (pin "TP") (pinfunction "TP_TP") (pintype "input"))
    )
    (net (code "66") (name "Net-(J9-Pad6)") (class "Default")
      (node (ref "J9") (pin "6") (pinfunction "6_6") (pintype "bidirectional"))
      (node (ref "TP3") (pin "TP") (pinfunction "TP_TP") (pintype "input"))
    )
    (net (code "67") (name "Net-(J9-Pad8)") (class "Default")
      (node (ref "J9") (pin "8") (pinfunction "8_8") (pintype "bidirectional"))
      (node (ref "TP4") (pin "TP") (pinfunction "TP_TP") (pintype "input"))
    )
    (net (code "68") (name "Net-(J9-Pad9)") (class "Default")
      (node (ref "J9") (pin "9") (pinfunction "9_9") (pintype "bidirectional"))
      (node (ref "TP18") (pin "TP") (pinfunction "TP_TP") (pintype "input"))
    )
    (net (code "69") (name "Net-(J9-Pad17)") (class "Default")
      (node (ref "J9") (pin "17") (pinfunction "17_17") (pintype "bidirectional"))
      (node (ref "TP19") (pin "TP") (pinfunction "TP_TP") (pintype "input"))
    )
    (net (code "70") (name "Net-(U4-EN)") (class "Default")
      (node (ref "R7") (pin "1") (pinfunction "1_1") (pintype "passive"))
      (node (ref "U4") (pin "7") (pinfunction "VREF2_7") (pintype "bidirectional"))
      (node (ref "U4") (pin "8") (pinfunction "EN_8") (pintype "bidirectional"))
    )
    (net (code "71") (name "Net-(U5-EN)") (class "Default")
      (node (ref "R8") (pin "1") (pinfunction "1_1") (pintype "passive"))
      (node (ref "U5") (pin "7") (pinfunction "VREF2_7") (pintype "bidirectional"))
      (node (ref "U5") (pin "8") (pinfunction "EN_8") (pintype "bidirectional"))
    )
    (net (code "72") (name "Net-(U6-EN)") (class "Default")
      (node (ref "C18") (pin "1") (pinfunction "1_1") (pintype "passive"))
      (node (ref "R9") (pin "1") (pinfunction "1_1") (pintype "passive"))
      (node (ref "U6") (pin "7") (pinfunction "VREF_B_7") (pintype "bidirectional"))
      (node (ref "U6") (pin "8") (pinfunction "EN_8") (pintype "bidirectional"))
    )
    (net (code "73") (name "Net-(U8-NR{slash}FB)") (class "Default")
      (node (ref "C10") (pin "1") (pinfunction "1_1") (pintype "passive"))
      (node (ref "R16") (pin "1") (pinfunction "1_1") (pintype "passive"))
      (node (ref "R17") (pin "1") (pinfunction "1_1") (pintype "passive"))
      (node (ref "U8") (pin "4") (pinfunction "NR/FB_4") (pintype "input"))
    )
    (net (code "74") (name "Net-(U9-CLKIN)") (class "Default")
      (node (ref "R24") (pin "2") (pinfunction "2_2") (pintype "passive"))
      (node (ref "R25") (pin "2") (pinfunction "2_2") (pintype "passive"))
      (node (ref "U9") (pin "1") (pinfunction "CLKIN_1") (pintype "bidirectional"))
    )
    (net (code "75") (name "Net-(U9-Y0)") (class "Default")
      (node (ref "R38") (pin "1") (pinfunction "1_1") (pintype "passive"))
      (node (ref "U9") (pin "3") (pinfunction "Y0_3") (pintype "bidirectional"))
    )
    (net (code "76") (name "Net-(U9-Y1)") (class "Default")
      (node (ref "R39") (pin "1") (pinfunction "1_1") (pintype "passive"))
      (node (ref "U9") (pin "8") (pinfunction "Y1_8") (pintype "bidirectional"))
    )
    (net (code "77") (name "Net-(U10-NR{slash}FB)") (class "Default")
      (node (ref "C19") (pin "1") (pinfunction "1_1") (pintype "passive"))
      (node (ref "U10") (pin "5") (pinfunction "NR/FB_5") (pintype "bidirectional"))
    )
    (net (code "78") (name "Net-(Y1-OUT)") (class "Default")
      (node (ref "R25") (pin "1") (pinfunction "1_1") (pintype "passive"))
      (node (ref "Y1") (pin "3") (pinfunction "OUT_3") (pintype "output"))
    )
    (net (code "79") (name "PWM1") (class "Default")
      (node (ref "J2") (pin "29") (pinfunction "GPIO-G_29") (pintype "bidirectional"))
      (node (ref "R6") (pin "1") (pinfunction "1_1") (pintype "passive"))
      (node (ref "U6") (pin "4") (pinfunction "A2_4") (pintype "bidirectional"))
    )
    (net (code "80") (name "PWM2") (class "Default")
      (node (ref "J2") (pin "30") (pinfunction "GPIO-H_30") (pintype "bidirectional"))
      (node (ref "R5") (pin "1") (pinfunction "1_1") (pintype "passive"))
      (node (ref "U6") (pin "3") (pinfunction "A1_3") (pintype "bidirectional"))
    )
    (net (code "81") (name "RST1") (class "Default")
      (node (ref "J2") (pin "31") (pinfunction "GPIO-I_31") (pintype "bidirectional"))
      (node (ref "U3") (pin "7") (pinfunction "A6_7") (pintype "bidirectional"))
    )
    (net (code "82") (name "RST2") (class "Default")
      (node (ref "J2") (pin "32") (pinfunction "GPIO-J_32") (pintype "bidirectional"))
      (node (ref "U3") (pin "6") (pinfunction "A5_6") (pintype "bidirectional"))
    )
    (net (code "83") (name "SPI0_CS") (class "Default")
      (node (ref "J2") (pin "12") (pinfunction "SPI0_CS_12") (pintype "bidirectional"))
      (node (ref "U2") (pin "4") (pinfunction "A3_4") (pintype "bidirectional"))
    )
    (net (code "84") (name "SPI0_CS1") (class "Default")
      (node (ref "J2") (pin "26") (pinfunction "GPIO-D_26") (pintype "bidirectional"))
      (node (ref "U3") (pin "8") (pinfunction "A7_8") (pintype "bidirectional"))
    )
    (net (code "85") (name "SPI0_CS2") (class "Default")
      (node (ref "J2") (pin "25") (pinfunction "GPIO-C_25") (pintype "bidirectional"))
      (node (ref "U3") (pin "9") (pinfunction "A8_9") (pintype "bidirectional"))
    )
    (net (code "86") (name "SPI0_DIN") (class "Default")
      (node (ref "J2") (pin "10") (pinfunction "SPI0_DIN_10") (pintype "bidirectional"))
      (node (ref "U2") (pin "6") (pinfunction "A5_6") (pintype "bidirectional"))
    )
    (net (code "87") (name "SPI0_DOUT") (class "Default")
      (node (ref "J2") (pin "14") (pinfunction "SPI0_DOUT_14") (pintype "bidirectional"))
      (node (ref "U2") (pin "1") (pinfunction "A1_1") (pintype "bidirectional"))
    )
    (net (code "88") (name "SPI0_SCLK") (class "Default")
      (node (ref "J2") (pin "8") (pinfunction "SPI0_SCLK_8") (pintype "bidirectional"))
      (node (ref "U2") (pin "7") (pinfunction "A6_7") (pintype "bidirectional"))
    )
    (net (code "89") (name "SPI_CS") (class "Default")
      (node (ref "J3") (pin "3") (pinfunction "CS_3") (pintype "bidirectional"))
      (node (ref "U2") (pin "17") (pinfunction "B3_17") (pintype "bidirectional"))
    )
    (net (code "90") (name "SPI_CS1") (class "Default")
      (node (ref "J4") (pin "3") (pinfunction "CS_3") (pintype "bidirectional"))
      (node (ref "U3") (pin "13") (pinfunction "B7_13") (pintype "bidirectional"))
    )
    (net (code "91") (name "SPI_CS2") (class "Default")
      (node (ref "U3") (pin "12") (pinfunction "B8_12") (pintype "bidirectional"))
      (node (ref "U7") (pin "1") (pinfunction "~{CS}/SHDN_1") (pintype "bidirectional"))
    )
    (net (code "92") (name "SPI_MISO") (class "Default")
      (node (ref "J3") (pin "5") (pinfunction "MISO_5") (pintype "bidirectional"))
      (node (ref "J4") (pin "5") (pinfunction "MISO_5") (pintype "bidirectional"))
      (node (ref "U2") (pin "15") (pinfunction "B5_15") (pintype "bidirectional"))
      (node (ref "U7") (pin "6") (pinfunction "DOUT_6") (pintype "bidirectional"))
    )
    (net (code "93") (name "SPI_MOSI") (class "Default")
      (node (ref "J3") (pin "6") (pinfunction "MOSI_6") (pintype "bidirectional"))
      (node (ref "J4") (pin "6") (pinfunction "MOSI_6") (pintype "bidirectional"))
      (node (ref "U2") (pin "20") (pinfunction "B1_20") (pintype "bidirectional"))
      (node (ref "U7") (pin "5") (pinfunction "DIN_5") (pintype "bidirectional"))
    )
    (net (code "94") (name "SPI_SCK") (class "Default")
      (node (ref "J3") (pin "4") (pinfunction "SCK_4") (pintype "bidirectional"))
      (node (ref "J4") (pin "4") (pinfunction "SCK_4") (pintype "bidirectional"))
      (node (ref "U2") (pin "14") (pinfunction "B6_14") (pintype "bidirectional"))
      (node (ref "U7") (pin "7") (pinfunction "CLK_7") (pintype "bidirectional"))
    )
    (net (code "95") (name "SYS_DCIN") (class "Default")
      (node (ref "J2") (pin "36") (pinfunction "SYS_DCIN_36") (pintype "bidirectional"))
      (node (ref "J2") (pin "38") (pinfunction "SYS_DCIN_38") (pintype "bidirectional"))
      (node (ref "TP21") (pin "TP") (pinfunction "TP_TP") (pintype "input"))
    )
    (net (code "96") (name "UART0_RX") (class "Default")
      (node (ref "J2") (pin "7") (pinfunction "UART0_RXD_7") (pintype "bidirectional"))
      (node (ref "U2") (pin "8") (pinfunction "A7_8") (pintype "bidirectional"))
    )
    (net (code "97") (name "UART0_TX") (class "Default")
      (node (ref "J2") (pin "5") (pinfunction "UART0_TXD_5") (pintype "bidirectional"))
      (node (ref "U2") (pin "9") (pinfunction "A8_9") (pintype "bidirectional"))
    )
    (net (code "98") (name "UART1_RX") (class "Default")
      (node (ref "J2") (pin "13") (pinfunction "UART1_RXD_13") (pintype "bidirectional"))
      (node (ref "U2") (pin "3") (pinfunction "A2_3") (pintype "bidirectional"))
    )
    (net (code "99") (name "UART1_TX") (class "Default")
      (node (ref "J2") (pin "11") (pinfunction "UART1_TXD_11") (pintype "bidirectional"))
      (node (ref "U2") (pin "5") (pinfunction "A4_5") (pintype "bidirectional"))
    )
    (net (code "100") (name "VREF") (class "Default")
      (node (ref "C8") (pin "2") (pinfunction "2_2") (pintype "passive"))
      (node (ref "L1") (pin "1") (pinfunction "1_1") (pintype "passive"))
      (node (ref "U7") (pin "8") (pinfunction "VDD/VREF_8") (pintype "bidirectional"))
    )
    (net (code "101") (name "unconnected-(J2-PCM_CLK-Pad18)") (class "Default")
      (node (ref "J2") (pin "18") (pinfunction "PCM_CLK_18") (pintype "bidirectional"))
    )
    (net (code "102") (name "unconnected-(J2-PCM_DI-Pad22)") (class "Default")
      (node (ref "J2") (pin "22") (pinfunction "PCM_DI_22") (pintype "bidirectional"))
    )
    (net (code "103") (name "unconnected-(J2-PCM_DO-Pad20)") (class "Default")
      (node (ref "J2") (pin "20") (pinfunction "PCM_DO_20") (pintype "bidirectional"))
    )
    (net (code "104") (name "unconnected-(J2-PCM_FS-Pad16)") (class "Default")
      (node (ref "J2") (pin "16") (pinfunction "PCM_FS_16") (pintype "bidirectional"))
    )
    (net (code "105") (name "unconnected-(J2-UART0_CTS-Pad3)") (class "Default")
      (node (ref "J2") (pin "3") (pinfunction "UART0_CTS_3") (pintype "bidirectional"))
    )
    (net (code "106") (name "unconnected-(J2-UART0_RTS-Pad9)") (class "Default")
      (node (ref "J2") (pin "9") (pinfunction "UART0_RTS_9") (pintype "bidirectional"))
    )
    (net (code "107") (name "unconnected-(J7-CLK1{slash}CSI1_MCLK-Pad17)") (class "Default")
      (node (ref "J7") (pin "17") (pinfunction "CLK1/CSI1_MCLK_17") (pintype "bidirectional"))
    )
    (net (code "108") (name "unconnected-(J7-DSI_D1+-Pad33)") (class "Default")
      (node (ref "J7") (pin "33") (pinfunction "DSI_D1+_33") (pintype "bidirectional"))
    )
    (net (code "109") (name "unconnected-(J7-DSI_D1--Pad35)") (class "Default")
      (node (ref "J7") (pin "35") (pinfunction "DSI_D1-_35") (pintype "bidirectional"))
    )
    (net (code "110") (name "unconnected-(J7-DSI_D2+-Pad39)") (class "Default")
      (node (ref "J7") (pin "39") (pinfunction "DSI_D2+_39") (pintype "bidirectional"))
    )
    (net (code "111") (name "unconnected-(J7-DSI_D2--Pad41)") (class "Default")
      (node (ref "J7") (pin "41") (pinfunction "DSI_D2-_41") (pintype "bidirectional"))
    )
    (net (code "112") (name "unconnected-(J7-DSI_D3+-Pad45)") (class "Default")
      (node (ref "J7") (pin "45") (pinfunction "DSI_D3+_45") (pintype "bidirectional"))
    )
    (net (code "113") (name "unconnected-(J7-DSI_D3--Pad47)") (class "Default")
      (node (ref "J7") (pin "47") (pinfunction "DSI_D3-_47") (pintype "bidirectional"))
    )
    (net (code "114") (name "unconnected-(J7-HSIC_DATA-Pad59)") (class "Default")
      (node (ref "J7") (pin "59") (pinfunction "HSIC_DATA_59") (pintype "bidirectional"))
    )
    (net (code "115") (name "unconnected-(J7-HSIC_STR-Pad57)") (class "Default")
      (node (ref "J7") (pin "57") (pinfunction "HSIC_STR_57") (pintype "bidirectional"))
    )
    (net (code "116") (name "unconnected-(J7-RESERVED-Pad60)") (class "Default")
      (node (ref "J7") (pin "60") (pinfunction "RESERVED_60") (pintype "bidirectional"))
    )
    (net (code "117") (name "unconnected-(J7-SD_CMD{slash}SPI1_DIN-Pad11)") (class "Default")
      (node (ref "J7") (pin "11") (pinfunction "SD_CMD/SPI1_DIN_11") (pintype "bidirectional"))
    )
    (net (code "118") (name "unconnected-(J7-SD_DAT0{slash}SPI1_DOUT-Pad1)") (class "Default")
      (node (ref "J7") (pin "1") (pinfunction "SD_DAT0/SPI1_DOUT_1") (pintype "bidirectional"))
    )
    (net (code "119") (name "unconnected-(J7-SD_DAT1-Pad3)") (class "Default")
      (node (ref "J7") (pin "3") (pinfunction "SD_DAT1_3") (pintype "bidirectional"))
    )
    (net (code "120") (name "unconnected-(J7-SD_DAT2-Pad5)") (class "Default")
      (node (ref "J7") (pin "5") (pinfunction "SD_DAT2_5") (pintype "bidirectional"))
    )
    (net (code "121") (name "unconnected-(J7-SD_DAT3{slash}SPI1_CS-Pad7)") (class "Default")
      (node (ref "J7") (pin "7") (pinfunction "SD_DAT3/SPI1_CS_7") (pintype "bidirectional"))
    )
    (net (code "122") (name "unconnected-(J7-SD_SCLK{slash}SPI1_SCLK-Pad9)") (class "Default")
      (node (ref "J7") (pin "9") (pinfunction "SD_SCLK/SPI1_SCLK_9") (pintype "bidirectional"))
    )
    (net (code "123") (name "unconnected-(J7-USB_D+-Pad51)") (class "Default")
      (node (ref "J7") (pin "51") (pinfunction "USB_D+_51") (pintype "bidirectional"))
    )
    (net (code "124") (name "unconnected-(J7-USB_D--Pad53)") (class "Default")
      (node (ref "J7") (pin "53") (pinfunction "USB_D-_53") (pintype "bidirectional"))
    )
    (net (code "125") (name "unconnected-(J8-Pad1)") (class "Default")
      (node (ref "J8") (pin "1") (pinfunction "1_1") (pintype "bidirectional"))
    )
    (net (code "126") (name "unconnected-(J8-Pad7)") (class "Default")
      (node (ref "J8") (pin "7") (pinfunction "7_7") (pintype "bidirectional"))
    )
    (net (code "127") (name "unconnected-(J8-Pad10)") (class "Default")
      (node (ref "J8") (pin "10") (pinfunction "10_10") (pintype "bidirectional"))
    )
    (net (code "128") (name "unconnected-(J8-Pad19)") (class "Default")
      (node (ref "J8") (pin "19") (pinfunction "19_19") (pintype "bidirectional"))
    )
    (net (code "129") (name "unconnected-(J8-Pad21)") (class "Default")
      (node (ref "J8") (pin "21") (pinfunction "21_21") (pintype "bidirectional"))
    )
    (net (code "130") (name "unconnected-(J8-Pad24)") (class "Default")
      (node (ref "J8") (pin "24") (pinfunction "24_24") (pintype "bidirectional"))
    )
    (net (code "131") (name "unconnected-(J9-Pad1)") (class "Default")
      (node (ref "J9") (pin "1") (pinfunction "1_1") (pintype "bidirectional"))
    )
    (net (code "132") (name "unconnected-(J9-Pad7)") (class "Default")
      (node (ref "J9") (pin "7") (pinfunction "7_7") (pintype "bidirectional"))
    )
    (net (code "133") (name "unconnected-(J9-Pad10)") (class "Default")
      (node (ref "J9") (pin "10") (pinfunction "10_10") (pintype "bidirectional"))
    )
    (net (code "134") (name "unconnected-(J9-Pad19)") (class "Default")
      (node (ref "J9") (pin "19") (pinfunction "19_19") (pintype "bidirectional"))
    )
    (net (code "135") (name "unconnected-(J9-Pad21)") (class "Default")
      (node (ref "J9") (pin "21") (pinfunction "21_21") (pintype "bidirectional"))
    )
    (net (code "136") (name "unconnected-(J9-Pad24)") (class "Default")
      (node (ref "J9") (pin "24") (pinfunction "24_24") (pintype "bidirectional"))
    )
    (net (code "137") (name "unconnected-(U3-A1-Pad1)") (class "Default")
      (node (ref "U3") (pin "1") (pinfunction "A1_1") (pintype "bidirectional"))
    )
    (net (code "138") (name "unconnected-(U3-A2-Pad3)") (class "Default")
      (node (ref "U3") (pin "3") (pinfunction "A2_3") (pintype "bidirectional"))
    )
    (net (code "139") (name "unconnected-(U3-B1-Pad20)") (class "Default")
      (node (ref "U3") (pin "20") (pinfunction "B1_20") (pintype "bidirectional"))
    )
    (net (code "140") (name "unconnected-(U3-B2-Pad18)") (class "Default")
      (node (ref "U3") (pin "18") (pinfunction "B2_18") (pintype "bidirectional"))
    )
    (net (code "141") (name "unconnected-(U9-NC-Pad5)") (class "Default")
      (node (ref "U9") (pin "5") (pinfunction "NC_5") (pintype "bidirectional"))
    )
    (net (code "142") (name "unconnected-(U9-NC-Pad7)") (class "Default")
      (node (ref "U9") (pin "7") (pinfunction "NC_7") (pintype "bidirectional"))
    )
    (net (code "143") (name "unconnected-(Y1-~{INH}-Pad1)") (class "Default")
      (node (ref "Y1") (pin "1") (pinfunction "~{INH}_1") (pintype "input"))
    )
  )
)
